# PowerBoardSchematic.net
KiCad netlist of a schematic drawn in Altium Designer
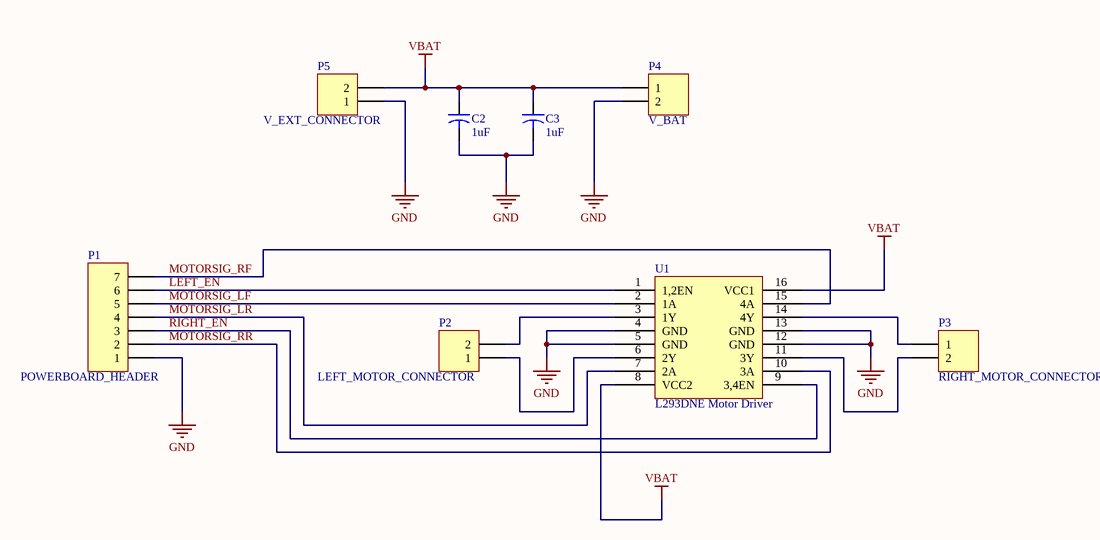
[diagram p0: PowerBoardSchematic.SchDoc]

(export (version "E")
  (design (tool "Eeschema 10.0.6"))
  (components
    (comp (ref "C2")
      (value "1uF")
      (footprint "CAPR5-4X5")
      (description "Capacitor")
      (fields (field (name "PUBLISHER") "Altium Limited"))
      (libsource (lib "Miscellaneous Devices") (part "Cap2"))
    )
    (comp (ref "C3")
      (value "1uF")
      (footprint "CAPR5-4X5")
      (description "Capacitor")
      (fields (field (name "PUBLISHER") "Altium Limited"))
      (libsource (lib "Miscellaneous Devices") (part "Cap2"))
    )
    (comp (ref "P1")
      (value "POWERBOARD_HEADER")
      (footprint "HDR1X7")
      (description "Header, 7-Pin")
      (fields (field (name "PUBLISHER") "Altium Limited"))
      (libsource (lib "Miscellaneous Connectors") (part "Header 7"))
    )
    (comp (ref "P2")
      (value "LEFT_MOTOR_CONNECTOR")
      (footprint "HDR1X2")
      (description "Header, 2-Pin")
      (fields (field (name "PUBLISHER") "Altium Limited"))
      (libsource (lib "Miscellaneous Connectors") (part "Header 2"))
    )
    (comp (ref "P3")
      (value "RIGHT_MOTOR_CONNECTOR")
      (footprint "HDR1X2")
      (description "Header, 2-Pin")
      (fields (field (name "PUBLISHER") "Altium Limited"))
      (libsource (lib "") (part "Header 2_1"))
    )
    (comp (ref "P4")
      (value "V_BAT")
      (footprint "HDR1X2")
      (description "Header, 2-Pin")
      (fields (field (name "PUBLISHER") "Altium Limited"))
      (libsource (lib "") (part "Header 2_1"))
    )
    (comp (ref "P5")
      (value "V_EXT_CONNECTOR")
      (footprint "HDR1X2")
      (description "Header, 2-Pin")
      (fields (field (name "PUBLISHER") "Altium Limited"))
      (libsource (lib "Miscellaneous Connectors") (part "Header 2"))
    )
    (comp (ref "U1")
      (value "L293DNE Motor Driver")
      (footprint "DIP16 (NE)")
      (description "TI L293DNE Quad H-bridge Motor Driver")
      (libsource (lib "L293DNE") (part "L293DNE"))
    )
  )
  (nets
    (net (code "1") (name "/LEFT_EN") (class "Default")
      (node (ref "P1") (pin "6") (pinfunction "6_6") (pintype "passive"))
      (node (ref "U1") (pin "1") (pinfunction "1,2EN_1") (pintype "passive"))
    )
    (net (code "2") (name "/MOTORSIG_LF") (class "Default")
      (node (ref "P1") (pin "5") (pinfunction "5_5") (pintype "passive"))
      (node (ref "U1") (pin "2") (pinfunction "1A_2") (pintype "passive"))
    )
    (net (code "3") (name "/MOTORSIG_LR") (class "Default")
      (node (ref "P1") (pin "4") (pinfunction "4_4") (pintype "passive"))
      (node (ref "U1") (pin "7") (pinfunction "2A_7") (pintype "passive"))
    )
    (net (code "4") (name "/MOTORSIG_RF") (class "Default")
      (node (ref "P1") (pin "7") (pinfunction "7_7") (pintype "passive"))
      (node (ref "U1") (pin "15") (pinfunction "4A_15") (pintype "passive"))
    )
    (net (code "5") (name "/MOTORSIG_RR") (class "Default")
      (node (ref "P1") (pin "2") (pinfunction "2_2") (pintype "passive"))
      (node (ref "U1") (pin "10") (pinfunction "3A_10") (pintype "passive"))
    )
    (net (code "6") (name "/RIGHT_EN") (class "Default")
      (node (ref "P1") (pin "3") (pinfunction "3_3") (pintype "passive"))
      (node (ref "U1") (pin "9") (pinfunction "3,4EN_9") (pintype "passive"))
    )
    (net (code "7") (name "GND") (class "Default")
      (node (ref "C2") (pin "2") (pinfunction "2_2") (pintype "passive"))
      (node (ref "C3") (pin "2") (pinfunction "2_2") (pintype "passive"))
      (node (ref "P1") (pin "1") (pinfunction "1_1") (pintype "passive"))
      (node (ref "P4") (pin "2") (pinfunction "2_2") (pintype "passive"))
      (node (ref "P5") (pin "1") (pinfunction "1_1") (pintype "passive"))
      (node (ref "U1") (pin "12") (pinfunction "GND_12") (pintype "passive"))
      (node (ref "U1") (pin "13") (pinfunction "GND_13") (pintype "passive"))
      (node (ref "U1") (pin "4") (pinfunction "GND_4") (pintype "passive"))
      (node (ref "U1") (pin "5") (pinfunction "GND_5") (pintype "passive"))
    )
    (net (code "8") (name "Net-(U1-1Y)") (class "Default")
      (node (ref "P2") (pin "2") (pinfunction "2_2") (pintype "passive"))
      (node (ref "U1") (pin "3") (pinfunction "1Y_3") (pintype "passive"))
    )
    (net (code "9") (name "Net-(U1-2Y)") (class "Default")
      (node (ref "P2") (pin "1") (pinfunction "1_1") (pintype "passive"))
      (node (ref "U1") (pin "6") (pinfunction "2Y_6") (pintype "passive"))
    )
    (net (code "10") (name "Net-(U1-3Y)") (class "Default")
      (node (ref "P3") (pin "2") (pinfunction "2_2") (pintype "passive"))
      (node (ref "U1") (pin "11") (pinfunction "3Y_11") (pintype "passive"))
    )
    (net (code "11") (name "Net-(U1-4Y)") (class "Default")
      (node (ref "P3") (pin "1") (pinfunction "1_1") (pintype "passive"))
      (node (ref "U1") (pin "14") (pinfunction "4Y_14") (pintype "passive"))
    )
    (net (code "12") (name "VBAT") (class "Default")
      (node (ref "C2") (pin "1") (pinfunction "1_1") (pintype "passive"))
      (node (ref "C3") (pin "1") (pinfunction "1_1") (pintype "passive"))
      (node (ref "P4") (pin "1") (pinfunction "1_1") (pintype "passive"))
      (node (ref "P5") (pin "2") (pinfunction "2_2") (pintype "passive"))
      (node (ref "U1") (pin "16") (pinfunction "VCC1_16") (pintype "passive"))
      (node (ref "U1") (pin "8") (pinfunction "VCC2_8") (pintype "passive"))
    )
  )
)
